# revC.net
KiCad netlist of a schematic drawn in EAGLE
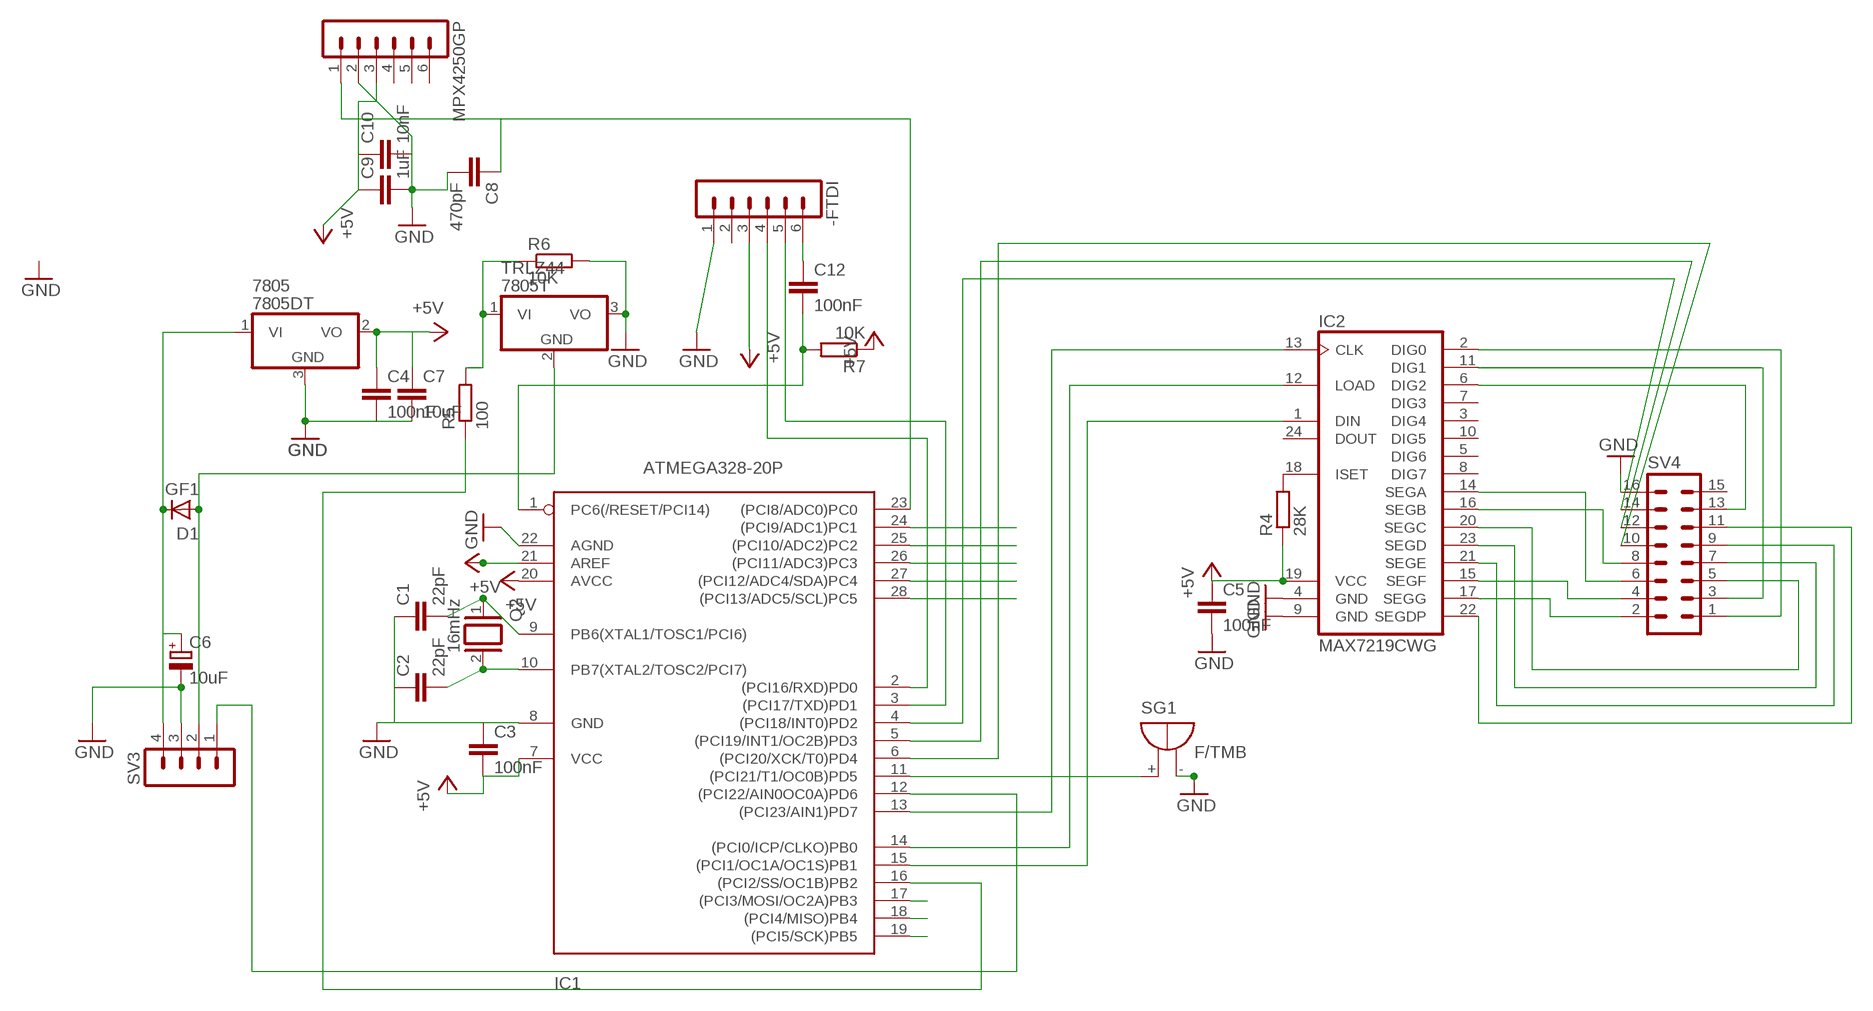
[diagram p0: schematic, sheet 1]

(export (version "E")
  (design (tool "Eeschema 10.0.6"))
  (components
    (comp (ref "-FTDI")
      (value "MA06-1")
      (footprint "eagle-import:MA06-1")
      (libsource (lib "eagle-import") (part "MA06-1"))
    )
    (comp (ref "7805")
      (value "7805DT")
      (footprint "eagle-import:TO252")
      (libsource (lib "eagle-import") (part "78DT05"))
    )
    (comp (ref "C1")
      (value "22pF")
      (footprint "eagle-import:C0805")
      (fields (field (name "MF") "MURATA") (field (name "MPN") "ERB21B5C2D220JDX1L"))
      (libsource (lib "eagle-import") (part "C-EUC0805"))
    )
    (comp (ref "C2")
      (value "22pF")
      (footprint "eagle-import:C0805")
      (fields (field (name "MF") "MURATA") (field (name "MPN") "ERB21B5C2D220JDX1L"))
      (libsource (lib "eagle-import") (part "C-EUC0805"))
    )
    (comp (ref "C3")
      (value "100nF")
      (footprint "eagle-import:C0805")
      (fields (field (name "MF") "KEMET") (field (name "MPN") "C0805X104K5RACTU"))
      (libsource (lib "eagle-import") (part "C-EUC0805"))
    )
    (comp (ref "C4")
      (value "100nF")
      (footprint "eagle-import:C0805")
      (fields (field (name "MF") "KEMET") (field (name "MPN") "C0805X104K5RACTU"))
      (libsource (lib "eagle-import") (part "C-EUC0805"))
    )
    (comp (ref "C5")
      (value "100nF")
      (footprint "eagle-import:C0805")
      (fields (field (name "MF") "KEMET") (field (name "MPN") "C0805X104K5RACTU"))
      (libsource (lib "eagle-import") (part "C-EUC0805"))
    )
    (comp (ref "C6")
      (value "10uF")
      (footprint "eagle-import:E2,5-6E")
      (libsource (lib "eagle-import") (part "CPOL-EUE2,5-6E"))
    )
    (comp (ref "C7")
      (value "10uF")
      (footprint "eagle-import:C0805")
      (fields (field (name "MF") "KEMET") (field (name "MPN") "C0805X104K5RACTU"))
      (libsource (lib "eagle-import") (part "C-EUC0805"))
    )
    (comp (ref "C8")
      (value "470pF")
      (footprint "eagle-import:C0805")
      (fields (field (name "MF") "KEMET") (field (name "MPN") "C0805X104K5RACTU"))
      (libsource (lib "eagle-import") (part "C-EUC0805"))
    )
    (comp (ref "C9")
      (value "1uF")
      (footprint "eagle-import:C0805")
      (fields (field (name "MF") "KEMET") (field (name "MPN") "C0805X104K5RACTU"))
      (libsource (lib "eagle-import") (part "C-EUC0805"))
    )
    (comp (ref "C10")
      (value "10nF")
      (footprint "eagle-import:C0805")
      (fields (field (name "MF") "KEMET") (field (name "MPN") "C0805X104K5RACTU"))
      (libsource (lib "eagle-import") (part "C-EUC0805"))
    )
    (comp (ref "C12")
      (value "100nF")
      (footprint "eagle-import:C0805")
      (fields (field (name "MF") "KEMET") (field (name "MPN") "C0805X104K5RACTU"))
      (libsource (lib "eagle-import") (part "C-EUC0805"))
    )
    (comp (ref "D1")
      (value "GF1")
      (footprint "eagle-import:SMA-DO214AC")
      (libsource (lib "eagle-import") (part "GF1"))
    )
    (comp (ref "IC1")
      (value "ATMEGA328-20P")
      (footprint "eagle-import:DIL28-3")
      (libsource (lib "eagle-import") (part "ATMEGA168P-20"))
    )
    (comp (ref "IC2")
      (value "MAX7219CWG")
      (footprint "eagle-import:MAX7219CWG")
      (libsource (lib "eagle-import") (part "MAX7219CWG"))
    )
    (comp (ref "MPX4250GP")
      (value "MA06-1")
      (footprint "eagle-import:MA06-1")
      (libsource (lib "eagle-import") (part "MA06-1"))
    )
    (comp (ref "Q2")
      (value "16mHz")
      (footprint "eagle-import:QS")
      (fields (field (name "MF") "EUROQUARTZ") (field (name "MPN") "16.000MHZ HC49/4H/30/50/40/18PF/ATF"))
      (libsource (lib "eagle-import") (part "XTAL/S"))
    )
    (comp (ref "R4")
      (value "28K")
      (footprint "eagle-import:R0805")
      (libsource (lib "eagle-import") (part "R-EU_R0805"))
    )
    (comp (ref "R5")
      (value "100")
      (footprint "eagle-import:R0805")
      (libsource (lib "eagle-import") (part "R-EU_R0805"))
    )
    (comp (ref "R6")
      (value "10K")
      (footprint "eagle-import:R0805")
      (libsource (lib "eagle-import") (part "R-EU_R0805"))
    )
    (comp (ref "R7")
      (value "10K")
      (footprint "eagle-import:R0805")
      (libsource (lib "eagle-import") (part "R-EU_R0805"))
    )
    (comp (ref "SG1")
      (value "F/TMB")
      (footprint "eagle-import:F_TMB")
      (libsource (lib "eagle-import") (part "F/TMB"))
    )
    (comp (ref "SV3")
      (value "MA04-1")
      (footprint "eagle-import:MA04-1")
      (libsource (lib "eagle-import") (part "MA04-1"))
    )
    (comp (ref "SV4")
      (value "MA08-2W")
      (footprint "eagle-import:MA08-2W")
      (libsource (lib "eagle-import") (part "MA08-2W"))
    )
    (comp (ref "TRLZ44")
      (value "7805T")
      (footprint "eagle-import:TO220H")
      (libsource (lib "eagle-import") (part "78T05"))
    )
  )
  (nets
    (net (code "1") (name "+5V") (class "Default")
      (node (ref "-FTDI") (pin "3") (pinfunction "3_3") (pintype "passive"))
      (node (ref "7805") (pin "2") (pinfunction "VO_2") (pintype "passive"))
      (node (ref "C10") (pin "1") (pinfunction "1_1") (pintype "passive"))
      (node (ref "C3") (pin "2") (pinfunction "2_2") (pintype "passive"))
      (node (ref "C4") (pin "1") (pinfunction "1_1") (pintype "passive"))
      (node (ref "C5") (pin "1") (pinfunction "1_1") (pintype "passive"))
      (node (ref "C7") (pin "1") (pinfunction "1_1") (pintype "passive"))
      (node (ref "C9") (pin "1") (pinfunction "1_1") (pintype "passive"))
      (node (ref "IC1") (pin "20") (pinfunction "AVCC_20") (pintype "bidirectional"))
      (node (ref "IC1") (pin "21") (pinfunction "AREF_21") (pintype "bidirectional"))
      (node (ref "IC1") (pin "7") (pinfunction "VCC_7") (pintype "bidirectional"))
      (node (ref "IC2") (pin "19") (pinfunction "VCC_19") (pintype "power_in"))
      (node (ref "MPX4250GP") (pin "3") (pinfunction "3_3") (pintype "passive"))
      (node (ref "R4") (pin "1") (pinfunction "1_1") (pintype "passive"))
      (node (ref "R7") (pin "1") (pinfunction "1_1") (pintype "passive"))
    )
    (net (code "2") (name "GND") (class "Default")
      (node (ref "-FTDI") (pin "1") (pinfunction "1_1") (pintype "passive"))
      (node (ref "7805") (pin "3") (pinfunction "GND_3") (pintype "passive"))
      (node (ref "C1") (pin "1") (pinfunction "1_1") (pintype "passive"))
      (node (ref "C10") (pin "2") (pinfunction "2_2") (pintype "passive"))
      (node (ref "C2") (pin "1") (pinfunction "1_1") (pintype "passive"))
      (node (ref "C3") (pin "1") (pinfunction "1_1") (pintype "passive"))
      (node (ref "C4") (pin "2") (pinfunction "2_2") (pintype "passive"))
      (node (ref "C5") (pin "2") (pinfunction "2_2") (pintype "passive"))
      (node (ref "C6") (pin "-") (pinfunction "-_-") (pintype "passive"))
      (node (ref "C7") (pin "2") (pinfunction "2_2") (pintype "passive"))
      (node (ref "C8") (pin "2") (pinfunction "2_2") (pintype "passive"))
      (node (ref "C9") (pin "2") (pinfunction "2_2") (pintype "passive"))
      (node (ref "IC1") (pin "22") (pinfunction "AGND_22") (pintype "bidirectional"))
      (node (ref "IC1") (pin "8") (pinfunction "GND_8") (pintype "bidirectional"))
      (node (ref "IC2") (pin "4") (pinfunction "GND_4") (pintype "power_in"))
      (node (ref "IC2") (pin "9") (pinfunction "GND_9") (pintype "power_in"))
      (node (ref "MPX4250GP") (pin "2") (pinfunction "2_2") (pintype "passive"))
      (node (ref "R6") (pin "2") (pinfunction "2_2") (pintype "passive"))
      (node (ref "SG1") (pin "-") (pinfunction "-_-") (pintype "passive"))
      (node (ref "SV3") (pin "3") (pinfunction "3_3") (pintype "passive"))
      (node (ref "SV4") (pin "16") (pinfunction "16_16") (pintype "passive"))
      (node (ref "TRLZ44") (pin "3") (pinfunction "VO_3") (pintype "passive"))
    )
    (net (code "3") (name "Net-(-FTDI-Pad6)") (class "Default")
      (node (ref "-FTDI") (pin "6") (pinfunction "6_6") (pintype "passive"))
      (node (ref "C12") (pin "1") (pinfunction "1_1") (pintype "passive"))
    )
    (net (code "4") (name "Net-(7805-VI)") (class "Default")
      (node (ref "7805") (pin "1") (pinfunction "VI_1") (pintype "input"))
      (node (ref "C6") (pin "+") (pinfunction "+_+") (pintype "passive"))
      (node (ref "D1") (pin "K") (pinfunction "C_K") (pintype "passive"))
      (node (ref "SV3") (pin "4") (pinfunction "4_4") (pintype "passive"))
    )
    (net (code "5") (name "Net-(IC1-(PCI0{slash}ICP{slash}CLKO)PB0)") (class "Default")
      (node (ref "IC1") (pin "14") (pinfunction "(PCI0/ICP/CLKO)PB0_14") (pintype "bidirectional"))
      (node (ref "IC2") (pin "12") (pinfunction "LOAD_12") (pintype "input"))
    )
    (net (code "6") (name "Net-(IC1-(PCI1{slash}OC1A{slash}OC1S)PB1)") (class "Default")
      (node (ref "IC1") (pin "15") (pinfunction "(PCI1/OC1A/OC1S)PB1_15") (pintype "bidirectional"))
      (node (ref "IC2") (pin "1") (pinfunction "DIN_1") (pintype "input"))
    )
    (net (code "7") (name "Net-(IC1-(PCI2{slash}SS{slash}OC1B)PB2)") (class "Default")
      (node (ref "IC1") (pin "16") (pinfunction "(PCI2/SS/OC1B)PB2_16") (pintype "bidirectional"))
      (node (ref "R5") (pin "1") (pinfunction "1_1") (pintype "passive"))
    )
    (net (code "8") (name "Net-(IC1-(PCI8{slash}ADC0)PC0)") (class "Default")
      (node (ref "C8") (pin "1") (pinfunction "1_1") (pintype "passive"))
      (node (ref "IC1") (pin "23") (pinfunction "(PCI8/ADC0)PC0_23") (pintype "bidirectional"))
      (node (ref "MPX4250GP") (pin "1") (pinfunction "1_1") (pintype "passive"))
    )
    (net (code "9") (name "Net-(IC1-(PCI16{slash}RXD)PD0)") (class "Default")
      (node (ref "-FTDI") (pin "4") (pinfunction "4_4") (pintype "passive"))
      (node (ref "IC1") (pin "2") (pinfunction "(PCI16/RXD)PD0_2") (pintype "bidirectional"))
    )
    (net (code "10") (name "Net-(IC1-(PCI17{slash}TXD)PD1)") (class "Default")
      (node (ref "-FTDI") (pin "5") (pinfunction "5_5") (pintype "passive"))
      (node (ref "IC1") (pin "3") (pinfunction "(PCI17/TXD)PD1_3") (pintype "bidirectional"))
    )
    (net (code "11") (name "Net-(IC1-(PCI18{slash}INT0)PD2)") (class "Default")
      (node (ref "IC1") (pin "4") (pinfunction "(PCI18/INT0)PD2_4") (pintype "bidirectional"))
      (node (ref "SV4") (pin "14") (pinfunction "14_14") (pintype "passive"))
    )
    (net (code "12") (name "Net-(IC1-(PCI19{slash}INT1{slash}OC2B)PD3)") (class "Default")
      (node (ref "IC1") (pin "5") (pinfunction "(PCI19/INT1/OC2B)PD3_5") (pintype "bidirectional"))
      (node (ref "SV4") (pin "12") (pinfunction "12_12") (pintype "passive"))
    )
    (net (code "13") (name "Net-(IC1-(PCI20{slash}XCK{slash}T0)PD4)") (class "Default")
      (node (ref "IC1") (pin "6") (pinfunction "(PCI20/XCK/T0)PD4_6") (pintype "bidirectional"))
      (node (ref "SV4") (pin "10") (pinfunction "10_10") (pintype "passive"))
    )
    (net (code "14") (name "Net-(IC1-(PCI21{slash}T1{slash}OC0B)PD5)") (class "Default")
      (node (ref "IC1") (pin "11") (pinfunction "(PCI21/T1/OC0B)PD5_11") (pintype "bidirectional"))
      (node (ref "SG1") (pin "+") (pinfunction "+_+") (pintype "passive"))
    )
    (net (code "15") (name "Net-(IC1-(PCI22{slash}AIN0OC0A)PD6)") (class "Default")
      (node (ref "IC1") (pin "12") (pinfunction "(PCI22/AIN0OC0A)PD6_12") (pintype "bidirectional"))
      (node (ref "SV3") (pin "1") (pinfunction "1_1") (pintype "passive"))
    )
    (net (code "16") (name "Net-(IC1-(PCI23{slash}AIN1)PD7)") (class "Default")
      (node (ref "IC1") (pin "13") (pinfunction "(PCI23/AIN1)PD7_13") (pintype "bidirectional"))
      (node (ref "IC2") (pin "13") (pinfunction "CLK_13") (pintype "input"))
    )
    (net (code "17") (name "Net-(IC1-PB6(XTAL1{slash}TOSC1{slash}PCI6))") (class "Default")
      (node (ref "C1") (pin "2") (pinfunction "2_2") (pintype "passive"))
      (node (ref "IC1") (pin "9") (pinfunction "PB6(XTAL1/TOSC1/PCI6)_9") (pintype "bidirectional"))
      (node (ref "Q2") (pin "1") (pinfunction "1_1") (pintype "passive"))
    )
    (net (code "18") (name "Net-(IC1-PB7(XTAL2{slash}TOSC2{slash}PCI7))") (class "Default")
      (node (ref "C2") (pin "2") (pinfunction "2_2") (pintype "passive"))
      (node (ref "IC1") (pin "10") (pinfunction "PB7(XTAL2/TOSC2/PCI7)_10") (pintype "bidirectional"))
      (node (ref "Q2") (pin "2") (pinfunction "2_2") (pintype "passive"))
    )
    (net (code "19") (name "Net-(IC1-PC6({slash}RESET{slash}PCI14))") (class "Default")
      (node (ref "C12") (pin "2") (pinfunction "2_2") (pintype "passive"))
      (node (ref "IC1") (pin "1") (pinfunction "PC6(/RESET/PCI14)_1") (pintype "bidirectional"))
      (node (ref "R7") (pin "2") (pinfunction "2_2") (pintype "passive"))
    )
    (net (code "20") (name "Net-(IC2-DIG0)") (class "Default")
      (node (ref "IC2") (pin "2") (pinfunction "DIG0_2") (pintype "output"))
      (node (ref "SV4") (pin "1") (pinfunction "1_1") (pintype "passive"))
    )
    (net (code "21") (name "Net-(IC2-DIG1)") (class "Default")
      (node (ref "IC2") (pin "11") (pinfunction "DIG1_11") (pintype "output"))
      (node (ref "SV4") (pin "3") (pinfunction "3_3") (pintype "passive"))
    )
    (net (code "22") (name "Net-(IC2-DIG2)") (class "Default")
      (node (ref "IC2") (pin "6") (pinfunction "DIG2_6") (pintype "output"))
      (node (ref "SV4") (pin "13") (pinfunction "13_13") (pintype "passive"))
    )
    (net (code "23") (name "Net-(IC2-ISET)") (class "Default")
      (node (ref "IC2") (pin "18") (pinfunction "ISET_18") (pintype "input"))
      (node (ref "R4") (pin "2") (pinfunction "2_2") (pintype "passive"))
    )
    (net (code "24") (name "Net-(IC2-SEGA)") (class "Default")
      (node (ref "IC2") (pin "14") (pinfunction "SEGA_14") (pintype "output"))
      (node (ref "SV4") (pin "6") (pinfunction "6_6") (pintype "passive"))
    )
    (net (code "25") (name "Net-(IC2-SEGB)") (class "Default")
      (node (ref "IC2") (pin "16") (pinfunction "SEGB_16") (pintype "output"))
      (node (ref "SV4") (pin "8") (pinfunction "8_8") (pintype "passive"))
    )
    (net (code "26") (name "Net-(IC2-SEGC)") (class "Default")
      (node (ref "IC2") (pin "20") (pinfunction "SEGC_20") (pintype "output"))
      (node (ref "SV4") (pin "5") (pinfunction "5_5") (pintype "passive"))
    )
    (net (code "27") (name "Net-(IC2-SEGD)") (class "Default")
      (node (ref "IC2") (pin "23") (pinfunction "SEGD_23") (pintype "output"))
      (node (ref "SV4") (pin "7") (pinfunction "7_7") (pintype "passive"))
    )
    (net (code "28") (name "Net-(IC2-SEGDP)") (class "Default")
      (node (ref "IC2") (pin "22") (pinfunction "SEGDP_22") (pintype "output"))
      (node (ref "SV4") (pin "11") (pinfunction "11_11") (pintype "passive"))
    )
    (net (code "29") (name "Net-(IC2-SEGE)") (class "Default")
      (node (ref "IC2") (pin "21") (pinfunction "SEGE_21") (pintype "output"))
      (node (ref "SV4") (pin "9") (pinfunction "9_9") (pintype "passive"))
    )
    (net (code "30") (name "Net-(IC2-SEGF)") (class "Default")
      (node (ref "IC2") (pin "15") (pinfunction "SEGF_15") (pintype "output"))
      (node (ref "SV4") (pin "4") (pinfunction "4_4") (pintype "passive"))
    )
    (net (code "31") (name "Net-(IC2-SEGG)") (class "Default")
      (node (ref "IC2") (pin "17") (pinfunction "SEGG_17") (pintype "output"))
      (node (ref "SV4") (pin "2") (pinfunction "2_2") (pintype "passive"))
    )
    (net (code "32") (name "Net-(TRLZ44-GND)") (class "Default")
      (node (ref "D1") (pin "A") (pinfunction "A_A") (pintype "passive"))
      (node (ref "SV3") (pin "2") (pinfunction "2_2") (pintype "passive"))
      (node (ref "TRLZ44") (pin "2") (pinfunction "GND_2") (pintype "passive"))
    )
    (net (code "33") (name "Net-(TRLZ44-VI)") (class "Default")
      (node (ref "R5") (pin "2") (pinfunction "2_2") (pintype "passive"))
      (node (ref "R6") (pin "1") (pinfunction "1_1") (pintype "passive"))
      (node (ref "TRLZ44") (pin "1") (pinfunction "VI_1") (pintype "input"))
    )
    (net (code "34") (name "unconnected-(-FTDI-Pad2)") (class "Default")
      (node (ref "-FTDI") (pin "2") (pinfunction "2_2") (pintype "passive"))
    )
    (net (code "35") (name "unconnected-(IC1-(PCI3{slash}MOSI{slash}OC2A)PB3-Pad17)") (class "Default")
      (node (ref "IC1") (pin "17") (pinfunction "(PCI3/MOSI/OC2A)PB3_17") (pintype "bidirectional"))
    )
    (net (code "36") (name "unconnected-(IC1-(PCI4{slash}MISO)PB4-Pad18)") (class "Default")
      (node (ref "IC1") (pin "18") (pinfunction "(PCI4/MISO)PB4_18") (pintype "bidirectional"))
    )
    (net (code "37") (name "unconnected-(IC1-(PCI5{slash}SCK)PB5-Pad19)") (class "Default")
      (node (ref "IC1") (pin "19") (pinfunction "(PCI5/SCK)PB5_19") (pintype "bidirectional"))
    )
    (net (code "38") (name "unconnected-(IC1-(PCI9{slash}ADC1)PC1-Pad24)") (class "Default")
      (node (ref "IC1") (pin "24") (pinfunction "(PCI9/ADC1)PC1_24") (pintype "bidirectional"))
    )
    (net (code "39") (name "unconnected-(IC1-(PCI10{slash}ADC2)PC2-Pad25)") (class "Default")
      (node (ref "IC1") (pin "25") (pinfunction "(PCI10/ADC2)PC2_25") (pintype "bidirectional"))
    )
    (net (code "40") (name "unconnected-(IC1-(PCI11{slash}ADC3)PC3-Pad26)") (class "Default")
      (node (ref "IC1") (pin "26") (pinfunction "(PCI11/ADC3)PC3_26") (pintype "bidirectional"))
    )
    (net (code "41") (name "unconnected-(IC1-(PCI12{slash}ADC4{slash}SDA)PC4-Pad27)") (class "Default")
      (node (ref "IC1") (pin "27") (pinfunction "(PCI12/ADC4/SDA)PC4_27") (pintype "bidirectional"))
    )
    (net (code "42") (name "unconnected-(IC1-(PCI13{slash}ADC5{slash}SCL)PC5-Pad28)") (class "Default")
      (node (ref "IC1") (pin "28") (pinfunction "(PCI13/ADC5/SCL)PC5_28") (pintype "bidirectional"))
    )
    (net (code "43") (name "unconnected-(IC2-DIG3-Pad7)") (class "Default")
      (node (ref "IC2") (pin "7") (pinfunction "DIG3_7") (pintype "output"))
    )
    (net (code "44") (name "unconnected-(IC2-DIG4-Pad3)") (class "Default")
      (node (ref "IC2") (pin "3") (pinfunction "DIG4_3") (pintype "output"))
    )
    (net (code "45") (name "unconnected-(IC2-DIG5-Pad10)") (class "Default")
      (node (ref "IC2") (pin "10") (pinfunction "DIG5_10") (pintype "output"))
    )
    (net (code "46") (name "unconnected-(IC2-DIG6-Pad5)") (class "Default")
      (node (ref "IC2") (pin "5") (pinfunction "DIG6_5") (pintype "output"))
    )
    (net (code "47") (name "unconnected-(IC2-DIG7-Pad8)") (class "Default")
      (node (ref "IC2") (pin "8") (pinfunction "DIG7_8") (pintype "output"))
    )
    (net (code "48") (name "unconnected-(IC2-DOUT-Pad24)") (class "Default")
      (node (ref "IC2") (pin "24") (pinfunction "DOUT_24") (pintype "output"))
    )
    (net (code "49") (name "unconnected-(MPX4250GP-Pad4)") (class "Default")
      (node (ref "MPX4250GP") (pin "4") (pinfunction "4_4") (pintype "passive"))
    )
    (net (code "50") (name "unconnected-(MPX4250GP-Pad5)") (class "Default")
      (node (ref "MPX4250GP") (pin "5") (pinfunction "5_5") (pintype "passive"))
    )
    (net (code "51") (name "unconnected-(MPX4250GP-Pad6)") (class "Default")
      (node (ref "MPX4250GP") (pin "6") (pinfunction "6_6") (pintype "passive"))
    )
    (net (code "52") (name "unconnected-(SV4-Pad15)") (class "Default")
      (node (ref "SV4") (pin "15") (pinfunction "15_15") (pintype "passive"))
    )
  )
)
